# ESP32-Programmer.net
KiCad netlist of a schematic drawn in EAGLE
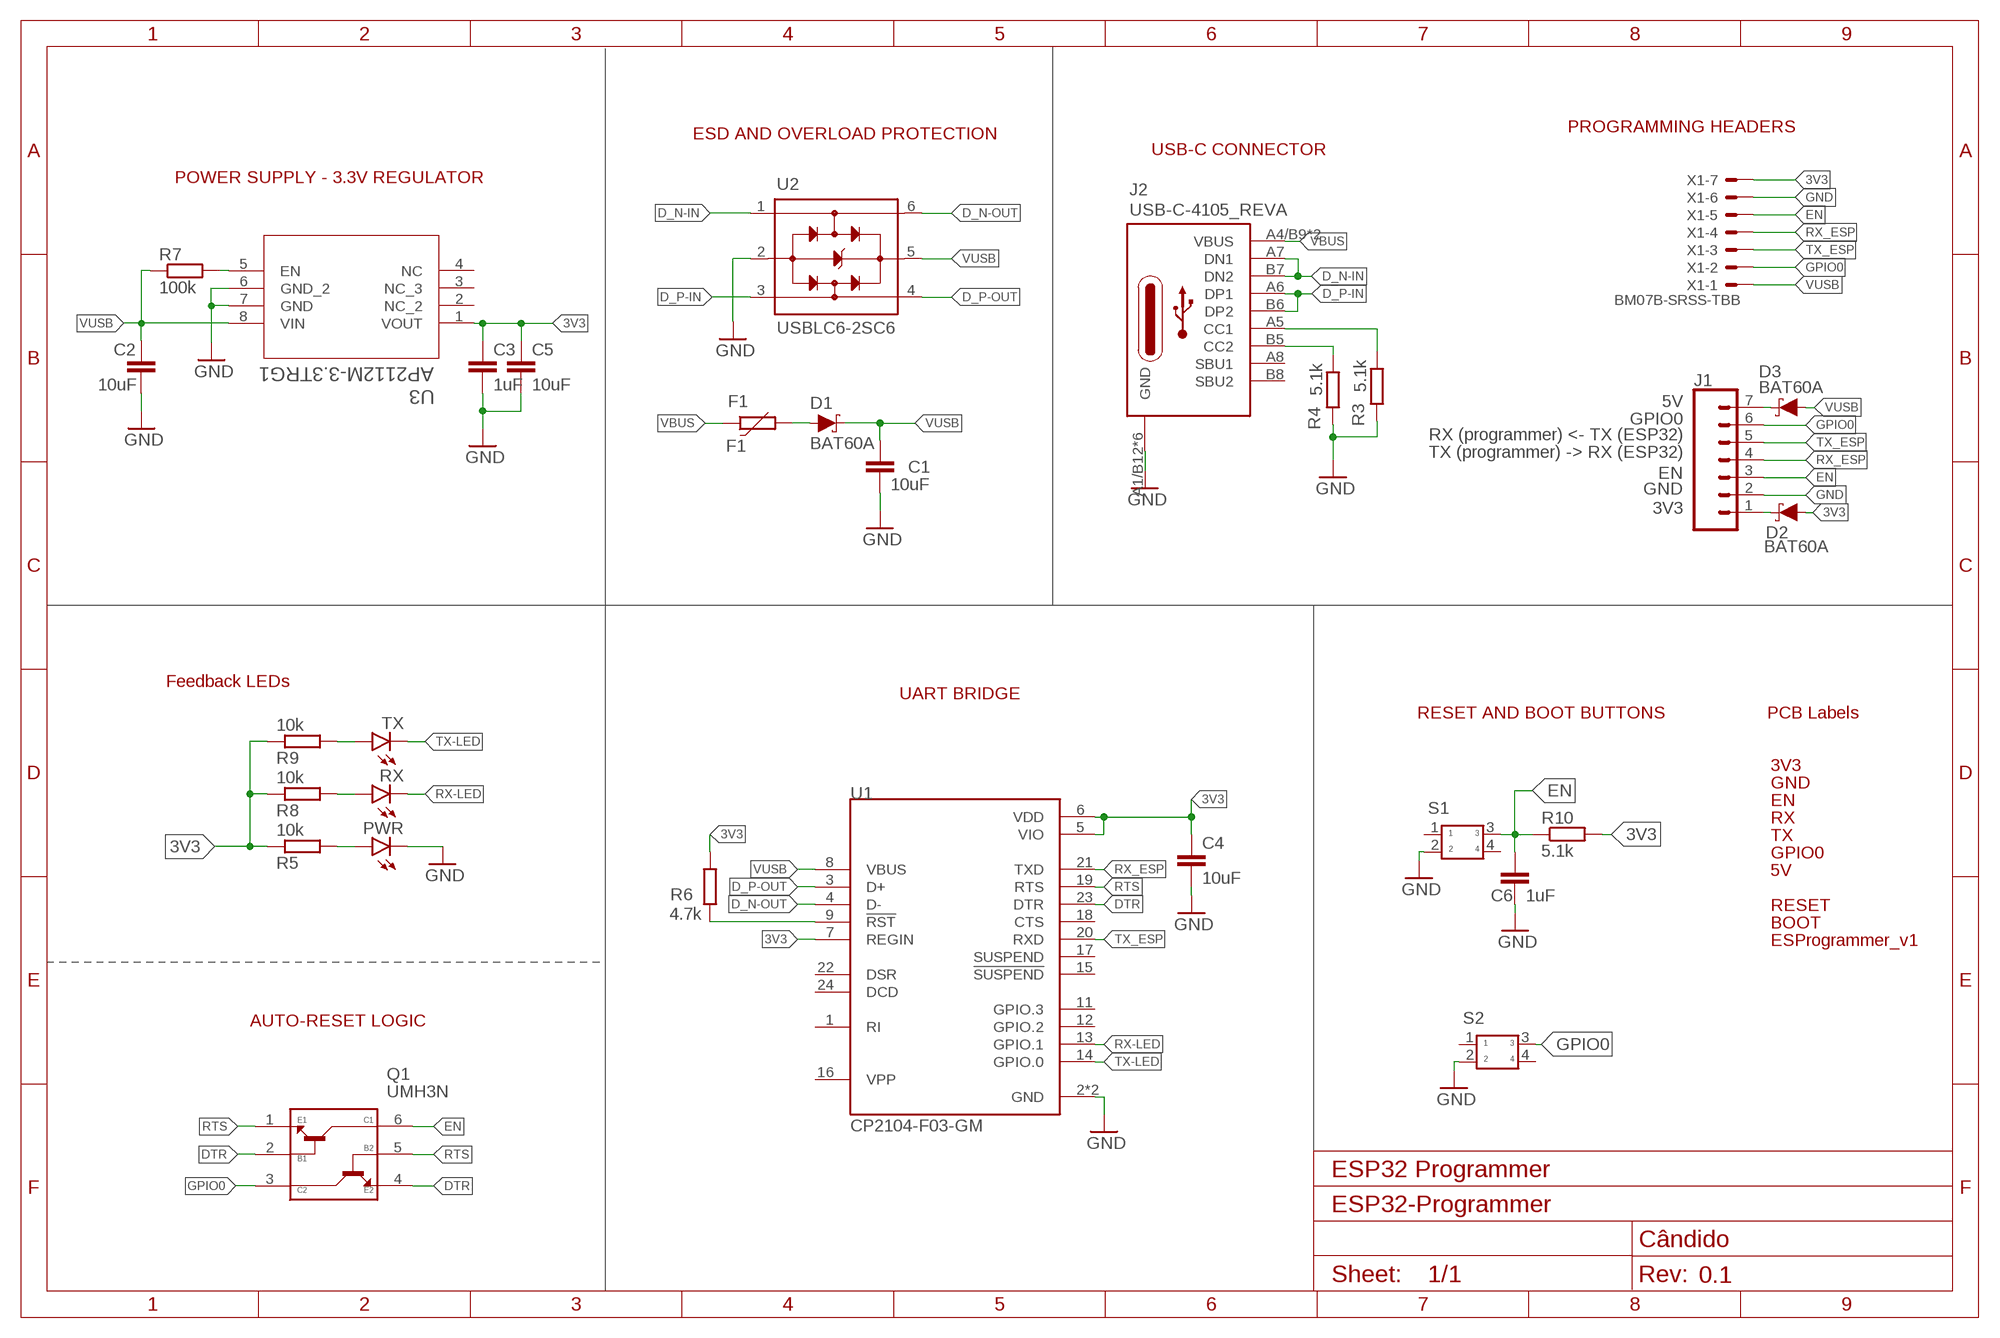
[diagram p0: schematic, sheet 1]

(export (version "E")
  (design (tool "Eeschema 10.0.6"))
  (components
    (comp (ref "C1")
      (value "10uF")
      (footprint "eagle-import:0603-CAP")
      (libsource (lib "eagle-import") (part "CAPACITOR0603-CAP"))
    )
    (comp (ref "C2")
      (value "10uF")
      (footprint "eagle-import:0603-CAP")
      (libsource (lib "eagle-import") (part "CAPACITOR0603-CAP"))
    )
    (comp (ref "C3")
      (value "1uF")
      (footprint "eagle-import:0603-CAP")
      (libsource (lib "eagle-import") (part "CAPACITOR0603-CAP"))
    )
    (comp (ref "C4")
      (value "10uF")
      (footprint "eagle-import:C0805")
      (libsource (lib "eagle-import") (part "C-EUC0805"))
    )
    (comp (ref "C5")
      (value "10uF")
      (footprint "eagle-import:0603-CAP")
      (libsource (lib "eagle-import") (part "CAPACITOR0603-CAP"))
    )
    (comp (ref "C6")
      (value "1uF")
      (footprint "eagle-import:C0805")
      (libsource (lib "eagle-import") (part "C-EUC0805"))
    )
    (comp (ref "D1")
      (value "BAT60A")
      (footprint "eagle-import:SOD-323")
      (libsource (lib "eagle-import") (part "DIODE-SCHOTTKY-BAT60A"))
    )
    (comp (ref "D2")
      (value "BAT60A")
      (footprint "eagle-import:SOD-323")
      (libsource (lib "eagle-import") (part "DIODE-SCHOTTKY-BAT60A"))
    )
    (comp (ref "D3")
      (value "BAT60A")
      (footprint "eagle-import:SOD-323")
      (libsource (lib "eagle-import") (part "DIODE-SCHOTTKY-BAT60A"))
    )
    (comp (ref "F1")
      (value "F1")
      (footprint "eagle-import:PTC1206")
      (libsource (lib "eagle-import") (part "PTC-FUSE"))
    )
    (comp (ref "FRAME1")
      (value "FRAME_A4")
      (footprint "eagle-import:FRAME-A4")
      (fields
        (field (name "CNAME") "ESP32 Programmer")
        (field (name "CREVISION") "0.1")
        (field (name "DESIGNER") "Cândido")
      )
      (libsource (lib "eagle-import") (part "FRAME_A4"))
    )
    (comp (ref "J1")
      (value "CONN-07NO_SILK")
      (footprint "eagle-import:1X07_NO_SILK")
      (libsource (lib "eagle-import") (part "CONN-07NO_SILK"))
    )
    (comp (ref "J2")
      (value "USB-C-4105_REVA")
      (footprint "eagle-import:GCT_USB4105_REVA")
      (fields
        (field (name "DIGI-KEY_PART_NUMBER") "2073-USB4105-GF-ACT-ND")
        (field (name "MF") "Global Connector Technology")
        (field (name "MP") "USB4105")
      )
      (libsource (lib "eagle-import") (part "USB-C-4105_REVA"))
    )
    (comp (ref "PWR")
      (value "LEDRED-0805")
      (footprint "eagle-import:LED_0805_RED")
      (libsource (lib "eagle-import") (part "LEDRED-0805"))
    )
    (comp (ref "Q1")
      (value "UMH3N")
      (footprint "eagle-import:SOT65P230X110-6N")
      (fields (field (name "MF") "Rohm"))
      (libsource (lib "eagle-import") (part "UMH3N"))
    )
    (comp (ref "R3")
      (value "5.1k")
      (footprint "eagle-import:R0805")
      (libsource (lib "eagle-import") (part "RESISTOR-EUR0805"))
    )
    (comp (ref "R4")
      (value "5.1k")
      (footprint "eagle-import:R0805")
      (libsource (lib "eagle-import") (part "RESISTOR-EUR0805"))
    )
    (comp (ref "R5")
      (value "10k")
      (footprint "eagle-import:R0805")
      (libsource (lib "eagle-import") (part "RESISTOR-EUR0805"))
    )
    (comp (ref "R6")
      (value "4.7k")
      (footprint "eagle-import:R0805")
      (libsource (lib "eagle-import") (part "RESISTOR-EUR0805"))
    )
    (comp (ref "R7")
      (value "100k")
      (footprint "eagle-import:R0805")
      (libsource (lib "eagle-import") (part "RESISTOR-EUR0805"))
    )
    (comp (ref "R8")
      (value "10k")
      (footprint "eagle-import:R0805")
      (libsource (lib "eagle-import") (part "RESISTOR-EUR0805"))
    )
    (comp (ref "R9")
      (value "10k")
      (footprint "eagle-import:R0805")
      (libsource (lib "eagle-import") (part "RESISTOR-EUR0805"))
    )
    (comp (ref "R10")
      (value "5.1k")
      (footprint "eagle-import:R0805")
      (libsource (lib "eagle-import") (part "RESISTOR-EUR0805"))
    )
    (comp (ref "RX")
      (value "LEDYELLOW-0805")
      (footprint "eagle-import:LED_0805_YELLOW")
      (libsource (lib "eagle-import") (part "LEDYELLOW-0805"))
    )
    (comp (ref "S1")
      (value "KMR621NG_LFS")
      (footprint "eagle-import:KMR621NG_LFS")
      (fields
        (field (name "ARROW_PART_NUMBER") "KMR621NG LFS")
        (field (name "MANUFACTURER") "C & K COMPONENTS")
        (field (name "RS_PART_NUMBER") "1359408")
      )
      (libsource (lib "eagle-import") (part "KMR621NG_LFS"))
    )
    (comp (ref "S2")
      (value "KMR621NG_LFS")
      (footprint "eagle-import:KMR621NG_LFS")
      (fields
        (field (name "ARROW_PART_NUMBER") "KMR621NG LFS")
        (field (name "MANUFACTURER") "C & K COMPONENTS")
        (field (name "RS_PART_NUMBER") "1359408")
      )
      (libsource (lib "eagle-import") (part "KMR621NG_LFS"))
    )
    (comp (ref "TX")
      (value "LEDORANGE-0805")
      (footprint "eagle-import:LED_0805_ORANGE")
      (libsource (lib "eagle-import") (part "LEDORANGE-0805"))
    )
    (comp (ref "U$1")
      (value "BOOT0")
      (footprint "eagle-import:BOOT0")
      (libsource (lib "eagle-import") (part "BOOT0"))
    )
    (comp (ref "U$2")
      (value "GND0")
      (footprint "eagle-import:GND0")
      (libsource (lib "eagle-import") (part "GND0"))
    )
    (comp (ref "U$3")
      (value "3V30")
      (footprint "eagle-import:3V30")
      (libsource (lib "eagle-import") (part "3V30"))
    )
    (comp (ref "U$4")
      (value "5V0")
      (footprint "eagle-import:5V0")
      (libsource (lib "eagle-import") (part "5V0"))
    )
    (comp (ref "U$5")
      (value "EN0")
      (footprint "eagle-import:EN0")
      (libsource (lib "eagle-import") (part "EN0"))
    )
    (comp (ref "U$6")
      (value "GPIO00")
      (footprint "eagle-import:GPIO00")
      (libsource (lib "eagle-import") (part "GPIO00"))
    )
    (comp (ref "U$7")
      (value "RX0")
      (footprint "eagle-import:RX0")
      (libsource (lib "eagle-import") (part "RX0"))
    )
    (comp (ref "U$8")
      (value "TX0")
      (footprint "eagle-import:TX0")
      (libsource (lib "eagle-import") (part "TX0"))
    )
    (comp (ref "U$9")
      (value "RESET0")
      (footprint "eagle-import:RESET0")
      (libsource (lib "eagle-import") (part "RESET0"))
    )
    (comp (ref "U$12")
      (value "ESPROGRAMMER_V10")
      (footprint "eagle-import:ESPROGRAMMER_V10")
      (libsource (lib "eagle-import") (part "ESPROGRAMMER_V10"))
    )
    (comp (ref "U1")
      (value "CP2104-F03-GM")
      (footprint "eagle-import:QFN50P400X400X80-25N")
      (fields (field (name "DIGI-KEY_PART_NUMBER") "336-2008-5-ND") (field (name "MF") "Silicon Labs"))
      (libsource (lib "eagle-import") (part "CP2104-F03-GM"))
    )
    (comp (ref "U2")
      (value "USBLC6-2SC6")
      (footprint "eagle-import:SOT95P280X145-6N")
      (fields (field (name "DIGI-KEY_PART_NUMBER") "497-5235-2-ND") (field (name "MF") "STMicroelectronics"))
      (libsource (lib "eagle-import") (part "USBLC6-2SC6"))
    )
    (comp (ref "U3")
      (value "AP2112M-3.3TRG1")
      (footprint "eagle-import:AP2112M-3.3TRG1_DIO")
      (fields (field (name "COPYRIGHT") "Copyright (C) 2022 Ultra Librarian. All rights reserved."))
      (libsource (lib "eagle-import") (part "AP2112M-3.3TRG1"))
    )
    (comp (ref "X1")
      (value "BM07B-SRSS-TBB")
      (footprint "eagle-import:BM07B-SRSS-TB")
      (libsource (lib "eagle-import") (part "BM07B-SRSS-TBB"))
    )
  )
  (nets
    (net (code "1") (name "3V3") (class "Default")
      (node (ref "C3") (pin "1") (pinfunction "1_1") (pintype "passive"))
      (node (ref "C4") (pin "1") (pinfunction "1_1") (pintype "passive"))
      (node (ref "C5") (pin "1") (pinfunction "1_1") (pintype "passive"))
      (node (ref "D2") (pin "A") (pinfunction "A_A") (pintype "passive"))
      (node (ref "R10") (pin "2") (pinfunction "2_2") (pintype "passive"))
      (node (ref "R5") (pin "1") (pinfunction "1_1") (pintype "passive"))
      (node (ref "R6") (pin "2") (pinfunction "2_2") (pintype "passive"))
      (node (ref "R8") (pin "1") (pinfunction "1_1") (pintype "passive"))
      (node (ref "R9") (pin "1") (pinfunction "1_1") (pintype "passive"))
      (node (ref "U1") (pin "5") (pinfunction "VIO_5") (pintype "power_in"))
      (node (ref "U1") (pin "6") (pinfunction "VDD_6") (pintype "power_in"))
      (node (ref "U1") (pin "7") (pinfunction "REGIN_7") (pintype "input"))
      (node (ref "U3") (pin "1") (pinfunction "VOUT_1") (pintype "output"))
      (node (ref "X1") (pin "7") (pinfunction "S_7") (pintype "passive"))
    )
    (net (code "2") (name "DTR") (class "Default")
      (node (ref "Q1") (pin "2") (pinfunction "B1_2") (pintype "bidirectional"))
      (node (ref "Q1") (pin "4") (pinfunction "E2_4") (pintype "bidirectional"))
      (node (ref "U1") (pin "23") (pinfunction "DTR_23") (pintype "output"))
    )
    (net (code "3") (name "D_N-IN") (class "Default")
      (node (ref "J2") (pin "A7") (pinfunction "DN1_A7") (pintype "bidirectional"))
      (node (ref "J2") (pin "B7") (pinfunction "DN2_B7") (pintype "bidirectional"))
      (node (ref "U2") (pin "1") (pinfunction "I/O1_IN_1") (pintype "bidirectional"))
    )
    (net (code "4") (name "D_N-OUT") (class "Default")
      (node (ref "U1") (pin "4") (pinfunction "D-_4") (pintype "bidirectional"))
      (node (ref "U2") (pin "6") (pinfunction "I/O1_OUT_6") (pintype "bidirectional"))
    )
    (net (code "5") (name "D_P-IN") (class "Default")
      (node (ref "J2") (pin "A6") (pinfunction "DP1_A6") (pintype "bidirectional"))
      (node (ref "J2") (pin "B6") (pinfunction "DP2_B6") (pintype "bidirectional"))
      (node (ref "U2") (pin "3") (pinfunction "I/O2_IN_3") (pintype "bidirectional"))
    )
    (net (code "6") (name "D_P-OUT") (class "Default")
      (node (ref "U1") (pin "3") (pinfunction "D+_3") (pintype "bidirectional"))
      (node (ref "U2") (pin "4") (pinfunction "I/O2_OUT_4") (pintype "bidirectional"))
    )
    (net (code "7") (name "EN") (class "Default")
      (node (ref "C6") (pin "1") (pinfunction "1_1") (pintype "passive"))
      (node (ref "J1") (pin "3") (pinfunction "3_3") (pintype "passive"))
      (node (ref "Q1") (pin "6") (pinfunction "C1_6") (pintype "bidirectional"))
      (node (ref "R10") (pin "1") (pinfunction "1_1") (pintype "passive"))
      (node (ref "S1") (pin "3") (pinfunction "3_3") (pintype "bidirectional"))
      (node (ref "X1") (pin "5") (pinfunction "S_5") (pintype "passive"))
    )
    (net (code "8") (name "GND") (class "Default")
      (node (ref "C1") (pin "2") (pinfunction "2_2") (pintype "passive"))
      (node (ref "C2") (pin "2") (pinfunction "2_2") (pintype "passive"))
      (node (ref "C3") (pin "2") (pinfunction "2_2") (pintype "passive"))
      (node (ref "C4") (pin "2") (pinfunction "2_2") (pintype "passive"))
      (node (ref "C5") (pin "2") (pinfunction "2_2") (pintype "passive"))
      (node (ref "C6") (pin "2") (pinfunction "2_2") (pintype "passive"))
      (node (ref "J1") (pin "2") (pinfunction "2_2") (pintype "passive"))
      (node (ref "J2") (pin "A1/B12") (pinfunction "GND_A1/B12") (pintype "power_in"))
      (node (ref "J2") (pin "B1/A12") (pinfunction "GND_B1/A12") (pintype "power_in"))
      (node (ref "J2") (pin "G1") (pinfunction "GND_G1") (pintype "power_in"))
      (node (ref "J2") (pin "G2") (pinfunction "GND_G2") (pintype "power_in"))
      (node (ref "J2") (pin "G3") (pinfunction "GND_G3") (pintype "power_in"))
      (node (ref "J2") (pin "G4") (pinfunction "GND_G4") (pintype "power_in"))
      (node (ref "PWR") (pin "C") (pinfunction "C_C") (pintype "passive"))
      (node (ref "R3") (pin "2") (pinfunction "2_2") (pintype "passive"))
      (node (ref "R4") (pin "2") (pinfunction "2_2") (pintype "passive"))
      (node (ref "S1") (pin "2") (pinfunction "2_2") (pintype "bidirectional"))
      (node (ref "S2") (pin "2") (pinfunction "2_2") (pintype "bidirectional"))
      (node (ref "U1") (pin "2") (pinfunction "GND_2") (pintype "power_in"))
      (node (ref "U1") (pin "25") (pinfunction "GND_25") (pintype "power_in"))
      (node (ref "U2") (pin "2") (pinfunction "GND_2") (pintype "power_in"))
      (node (ref "U3") (pin "6") (pinfunction "GND_2_6") (pintype "passive"))
      (node (ref "U3") (pin "7") (pinfunction "GND_7") (pintype "passive"))
      (node (ref "X1") (pin "6") (pinfunction "S_6") (pintype "passive"))
    )
    (net (code "9") (name "GPIO0") (class "Default")
      (node (ref "J1") (pin "6") (pinfunction "6_6") (pintype "passive"))
      (node (ref "Q1") (pin "3") (pinfunction "C2_3") (pintype "bidirectional"))
      (node (ref "S2") (pin "3") (pinfunction "3_3") (pintype "bidirectional"))
      (node (ref "X1") (pin "2") (pinfunction "S_2") (pintype "passive"))
    )
    (net (code "10") (name "Net-(D1-PadA)") (class "Default")
      (node (ref "D1") (pin "A") (pinfunction "A_A") (pintype "passive"))
      (node (ref "F1") (pin "2") (pinfunction "2_2") (pintype "passive"))
    )
    (net (code "11") (name "Net-(D2-PadC)") (class "Default")
      (node (ref "D2") (pin "C") (pinfunction "C_C") (pintype "passive"))
      (node (ref "J1") (pin "1") (pinfunction "1_1") (pintype "passive"))
    )
    (net (code "12") (name "Net-(D3-PadC)") (class "Default")
      (node (ref "D3") (pin "C") (pinfunction "C_C") (pintype "passive"))
      (node (ref "J1") (pin "7") (pinfunction "7_7") (pintype "passive"))
    )
    (net (code "13") (name "Net-(J2-CC1)") (class "Default")
      (node (ref "J2") (pin "A5") (pinfunction "CC1_A5") (pintype "bidirectional"))
      (node (ref "R3") (pin "1") (pinfunction "1_1") (pintype "passive"))
    )
    (net (code "14") (name "Net-(J2-CC2)") (class "Default")
      (node (ref "J2") (pin "B5") (pinfunction "CC2_B5") (pintype "bidirectional"))
      (node (ref "R4") (pin "1") (pinfunction "1_1") (pintype "passive"))
    )
    (net (code "15") (name "Net-(PWR-PadA)") (class "Default")
      (node (ref "PWR") (pin "A") (pinfunction "A_A") (pintype "passive"))
      (node (ref "R5") (pin "2") (pinfunction "2_2") (pintype "passive"))
    )
    (net (code "16") (name "Net-(R8-Pad2)") (class "Default")
      (node (ref "R8") (pin "2") (pinfunction "2_2") (pintype "passive"))
      (node (ref "RX") (pin "A") (pinfunction "A_A") (pintype "passive"))
    )
    (net (code "17") (name "Net-(R9-Pad2)") (class "Default")
      (node (ref "R9") (pin "2") (pinfunction "2_2") (pintype "passive"))
      (node (ref "TX") (pin "A") (pinfunction "A_A") (pintype "passive"))
    )
    (net (code "18") (name "Net-(U1-~{RST})") (class "Default")
      (node (ref "R6") (pin "1") (pinfunction "1_1") (pintype "passive"))
      (node (ref "U1") (pin "9") (pinfunction "~{RST}_9") (pintype "input"))
    )
    (net (code "19") (name "Net-(U3-EN)") (class "Default")
      (node (ref "R7") (pin "2") (pinfunction "2_2") (pintype "passive"))
      (node (ref "U3") (pin "5") (pinfunction "EN_5") (pintype "passive"))
    )
    (net (code "20") (name "RTS") (class "Default")
      (node (ref "Q1") (pin "1") (pinfunction "E1_1") (pintype "bidirectional"))
      (node (ref "Q1") (pin "5") (pinfunction "B2_5") (pintype "bidirectional"))
      (node (ref "U1") (pin "19") (pinfunction "RTS_19") (pintype "output"))
    )
    (net (code "21") (name "RX-LED") (class "Default")
      (node (ref "RX") (pin "C") (pinfunction "C_C") (pintype "passive"))
      (node (ref "U1") (pin "13") (pinfunction "GPIO.1_13") (pintype "bidirectional"))
    )
    (net (code "22") (name "RX_ESP") (class "Default")
      (node (ref "J1") (pin "4") (pinfunction "4_4") (pintype "passive"))
      (node (ref "U1") (pin "21") (pinfunction "TXD_21") (pintype "output"))
      (node (ref "X1") (pin "4") (pinfunction "S_4") (pintype "passive"))
    )
    (net (code "23") (name "TX-LED") (class "Default")
      (node (ref "TX") (pin "C") (pinfunction "C_C") (pintype "passive"))
      (node (ref "U1") (pin "14") (pinfunction "GPIO.0_14") (pintype "bidirectional"))
    )
    (net (code "24") (name "TX_ESP") (class "Default")
      (node (ref "J1") (pin "5") (pinfunction "5_5") (pintype "passive"))
      (node (ref "U1") (pin "20") (pinfunction "RXD_20") (pintype "input"))
      (node (ref "X1") (pin "3") (pinfunction "S_3") (pintype "passive"))
    )
    (net (code "25") (name "VBUS") (class "Default")
      (node (ref "F1") (pin "1") (pinfunction "1_1") (pintype "passive"))
      (node (ref "J2") (pin "A4/B9") (pinfunction "VBUS_A4/B9") (pintype "power_in"))
      (node (ref "J2") (pin "B4/A9") (pinfunction "VBUS_B4/A9") (pintype "power_in"))
    )
    (net (code "26") (name "VUSB") (class "Default")
      (node (ref "C1") (pin "1") (pinfunction "1_1") (pintype "passive"))
      (node (ref "C2") (pin "1") (pinfunction "1_1") (pintype "passive"))
      (node (ref "D1") (pin "C") (pinfunction "C_C") (pintype "passive"))
      (node (ref "D3") (pin "A") (pinfunction "A_A") (pintype "passive"))
      (node (ref "R7") (pin "1") (pinfunction "1_1") (pintype "passive"))
      (node (ref "U1") (pin "8") (pinfunction "VBUS_8") (pintype "input"))
      (node (ref "U2") (pin "5") (pinfunction "VBUS_5") (pintype "power_in"))
      (node (ref "U3") (pin "8") (pinfunction "VIN_8") (pintype "power_in"))
      (node (ref "X1") (pin "1") (pinfunction "S_1") (pintype "passive"))
    )
    (net (code "27") (name "unconnected-(J2-SBU1-PadA8)") (class "Default")
      (node (ref "J2") (pin "A8") (pinfunction "SBU1_A8") (pintype "bidirectional"))
    )
    (net (code "28") (name "unconnected-(J2-SBU2-PadB8)") (class "Default")
      (node (ref "J2") (pin "B8") (pinfunction "SBU2_B8") (pintype "bidirectional"))
    )
    (net (code "29") (name "unconnected-(S1-Pad1)") (class "Default")
      (node (ref "S1") (pin "1") (pinfunction "1_1") (pintype "bidirectional"))
    )
    (net (code "30") (name "unconnected-(S1-Pad4)") (class "Default")
      (node (ref "S1") (pin "4") (pinfunction "4_4") (pintype "bidirectional"))
    )
    (net (code "31") (name "unconnected-(S2-Pad1)") (class "Default")
      (node (ref "S2") (pin "1") (pinfunction "1_1") (pintype "bidirectional"))
    )
    (net (code "32") (name "unconnected-(S2-Pad4)") (class "Default")
      (node (ref "S2") (pin "4") (pinfunction "4_4") (pintype "bidirectional"))
    )
    (net (code "33") (name "unconnected-(U1-CTS-Pad18)") (class "Default")
      (node (ref "U1") (pin "18") (pinfunction "CTS_18") (pintype "input"))
    )
    (net (code "34") (name "unconnected-(U1-DCD-Pad24)") (class "Default")
      (node (ref "U1") (pin "24") (pinfunction "DCD_24") (pintype "input"))
    )
    (net (code "35") (name "unconnected-(U1-DSR-Pad22)") (class "Default")
      (node (ref "U1") (pin "22") (pinfunction "DSR_22") (pintype "input"))
    )
    (net (code "36") (name "unconnected-(U1-GPIO.2-Pad12)") (class "Default")
      (node (ref "U1") (pin "12") (pinfunction "GPIO.2_12") (pintype "bidirectional"))
    )
    (net (code "37") (name "unconnected-(U1-GPIO.3-Pad11)") (class "Default")
      (node (ref "U1") (pin "11") (pinfunction "GPIO.3_11") (pintype "bidirectional"))
    )
    (net (code "38") (name "unconnected-(U1-RI-Pad1)") (class "Default")
      (node (ref "U1") (pin "1") (pinfunction "RI_1") (pintype "input"))
    )
    (net (code "39") (name "unconnected-(U1-SUSPEND-Pad17)") (class "Default")
      (node (ref "U1") (pin "17") (pinfunction "SUSPEND_17") (pintype "output"))
    )
    (net (code "40") (name "unconnected-(U1-VPP-Pad16)") (class "Default")
      (node (ref "U1") (pin "16") (pinfunction "VPP_16") (pintype "passive"))
    )
    (net (code "41") (name "unconnected-(U1-~{SUSPEND}-Pad15)") (class "Default")
      (node (ref "U1") (pin "15") (pinfunction "~{SUSPEND}_15") (pintype "output"))
    )
    (net (code "42") (name "unconnected-(U3-NC-Pad4)") (class "Default")
      (node (ref "U3") (pin "4") (pinfunction "NC_4") (pintype "no_connect"))
    )
    (net (code "43") (name "unconnected-(U3-NC_2-Pad2)") (class "Default")
      (node (ref "U3") (pin "2") (pinfunction "NC_2_2") (pintype "no_connect"))
    )
    (net (code "44") (name "unconnected-(U3-NC_3-Pad3)") (class "Default")
      (node (ref "U3") (pin "3") (pinfunction "NC_3_3") (pintype "no_connect"))
    )
  )
)
